# SOIC16.net
KiCad netlist of a schematic drawn in EAGLE
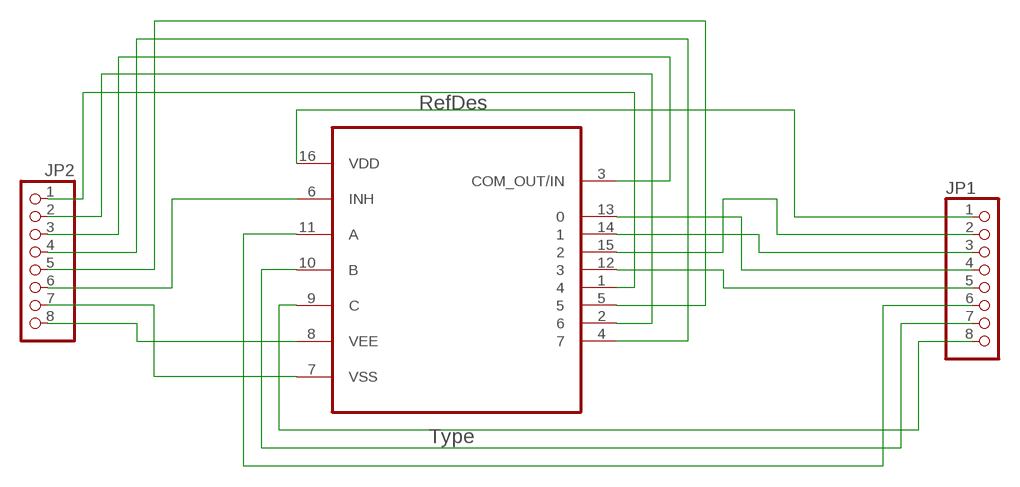
[diagram p0: schematic, sheet 1]

(export (version "E")
  (design (tool "Eeschema 10.0.6"))
  (components
    (comp (ref "JP1")
      (value "PINHD-1X8")
      (footprint "eagle-import:1X08")
      (libsource (lib "eagle-import") (part "PINHD-1X8"))
    )
    (comp (ref "JP2")
      (value "PINHD-1X8")
      (footprint "eagle-import:1X08")
      (libsource (lib "eagle-import") (part "PINHD-1X8"))
    )
    (comp (ref "U1")
      (value "CD4051BM")
      (footprint "eagle-import:SOIC127P600X175-16N")
      (libsource (lib "eagle-import") (part "CD4051BM"))
    )
  )
  (nets
    (net (code "1") (name "Net-(JP2-Pad5)") (class "Default")
      (node (ref "JP2") (pin "5") (pinfunction "5_5") (pintype "passive"))
      (node (ref "U1") (pin "5") (pinfunction "5_5") (pintype "bidirectional"))
    )
    (net (code "2") (name "Net-(U1-0)") (class "Default")
      (node (ref "JP1") (pin "4") (pinfunction "4_4") (pintype "passive"))
      (node (ref "U1") (pin "13") (pinfunction "0_13") (pintype "bidirectional"))
    )
    (net (code "3") (name "Net-(U1-1)") (class "Default")
      (node (ref "JP1") (pin "3") (pinfunction "3_3") (pintype "passive"))
      (node (ref "U1") (pin "14") (pinfunction "1_14") (pintype "bidirectional"))
    )
    (net (code "4") (name "Net-(U1-2)") (class "Default")
      (node (ref "JP1") (pin "2") (pinfunction "2_2") (pintype "passive"))
      (node (ref "U1") (pin "15") (pinfunction "2_15") (pintype "bidirectional"))
    )
    (net (code "5") (name "Net-(U1-3)") (class "Default")
      (node (ref "JP1") (pin "5") (pinfunction "5_5") (pintype "passive"))
      (node (ref "U1") (pin "12") (pinfunction "3_12") (pintype "bidirectional"))
    )
    (net (code "6") (name "Net-(U1-4)") (class "Default")
      (node (ref "JP2") (pin "1") (pinfunction "1_1") (pintype "passive"))
      (node (ref "U1") (pin "1") (pinfunction "4_1") (pintype "bidirectional"))
    )
    (net (code "7") (name "Net-(U1-6)") (class "Default")
      (node (ref "JP2") (pin "2") (pinfunction "2_2") (pintype "passive"))
      (node (ref "U1") (pin "2") (pinfunction "6_2") (pintype "bidirectional"))
    )
    (net (code "8") (name "Net-(U1-7)") (class "Default")
      (node (ref "JP2") (pin "4") (pinfunction "4_4") (pintype "passive"))
      (node (ref "U1") (pin "4") (pinfunction "7_4") (pintype "bidirectional"))
    )
    (net (code "9") (name "Net-(U1-A)") (class "Default")
      (node (ref "JP1") (pin "6") (pinfunction "6_6") (pintype "passive"))
      (node (ref "U1") (pin "11") (pinfunction "A_11") (pintype "input"))
    )
    (net (code "10") (name "Net-(U1-B)") (class "Default")
      (node (ref "JP1") (pin "7") (pinfunction "7_7") (pintype "passive"))
      (node (ref "U1") (pin "10") (pinfunction "B_10") (pintype "input"))
    )
    (net (code "11") (name "Net-(U1-C)") (class "Default")
      (node (ref "JP1") (pin "8") (pinfunction "8_8") (pintype "passive"))
      (node (ref "U1") (pin "9") (pinfunction "C_9") (pintype "bidirectional"))
    )
    (net (code "12") (name "Net-(U1-COM_OUT{slash}IN)") (class "Default")
      (node (ref "JP2") (pin "3") (pinfunction "3_3") (pintype "passive"))
      (node (ref "U1") (pin "3") (pinfunction "COM_OUT/IN_3") (pintype "bidirectional"))
    )
    (net (code "13") (name "Net-(U1-INH)") (class "Default")
      (node (ref "JP2") (pin "6") (pinfunction "6_6") (pintype "passive"))
      (node (ref "U1") (pin "6") (pinfunction "INH_6") (pintype "input"))
    )
    (net (code "14") (name "Net-(U1-VDD)") (class "Default")
      (node (ref "JP1") (pin "1") (pinfunction "1_1") (pintype "passive"))
      (node (ref "U1") (pin "16") (pinfunction "VDD_16") (pintype "input"))
    )
    (net (code "15") (name "Net-(U1-VEE)") (class "Default")
      (node (ref "JP2") (pin "8") (pinfunction "8_8") (pintype "passive"))
      (node (ref "U1") (pin "8") (pinfunction "VEE_8") (pintype "power_in"))
    )
    (net (code "16") (name "Net-(U1-VSS)") (class "Default")
      (node (ref "JP2") (pin "7") (pinfunction "7_7") (pintype "passive"))
      (node (ref "U1") (pin "7") (pinfunction "VSS_7") (pintype "power_in"))
    )
  )
)
